# T32_ref.net
KiCad netlist of a schematic drawn in EAGLE
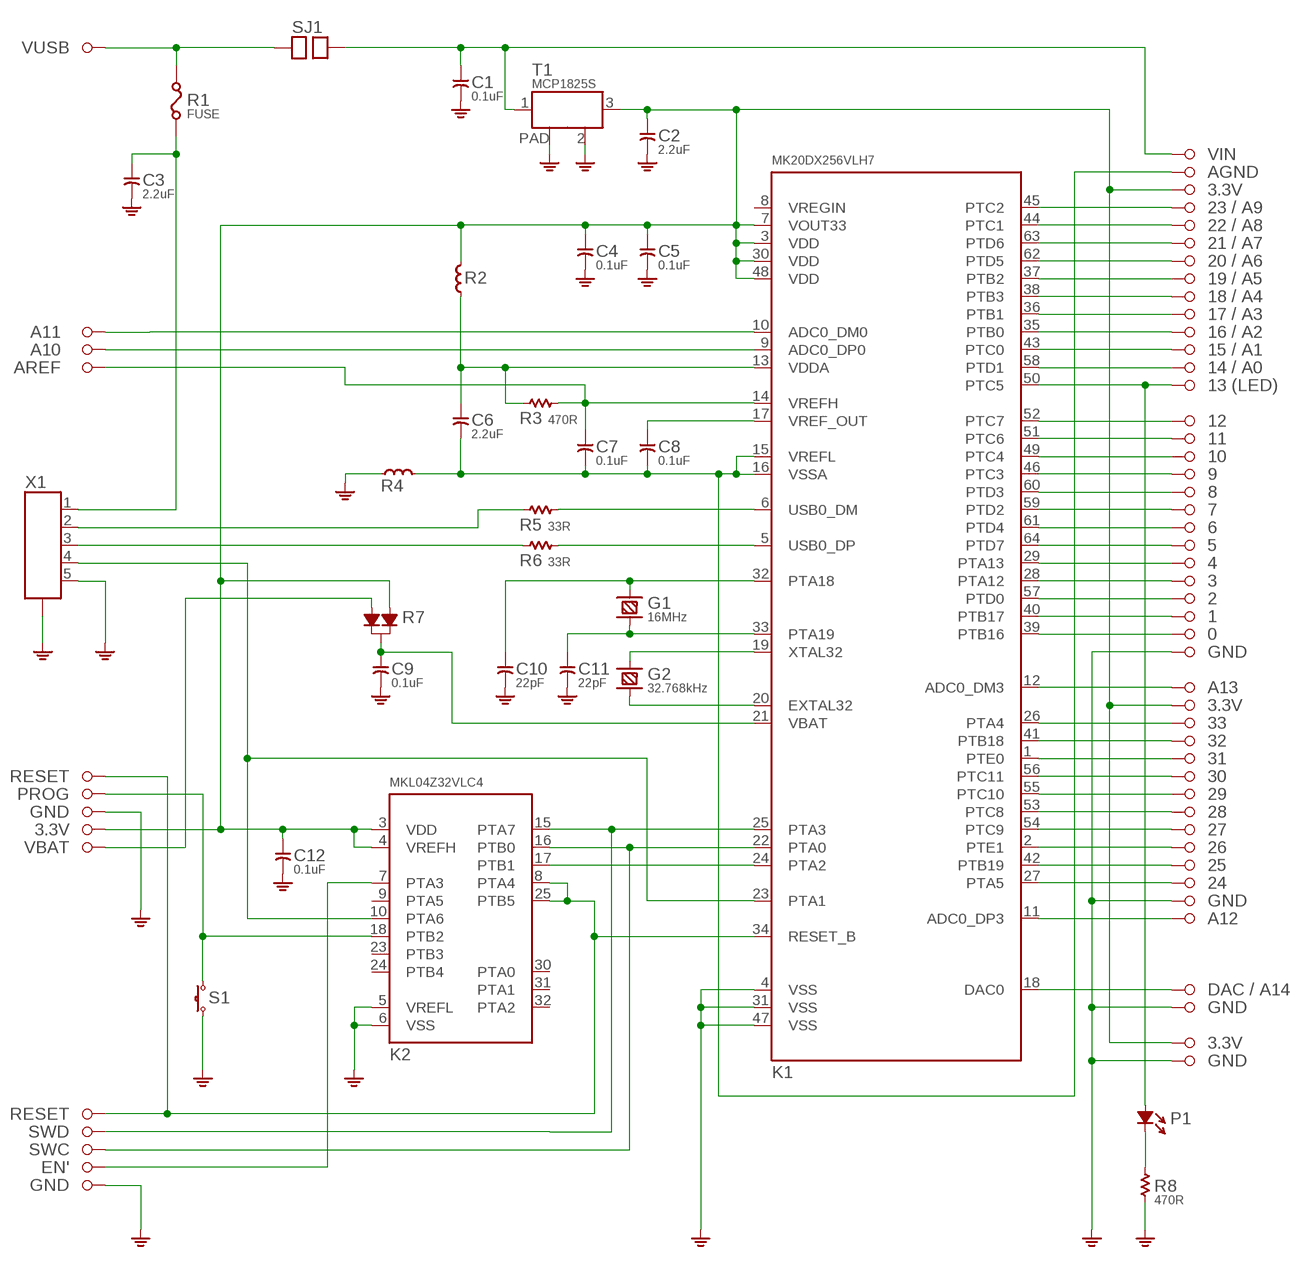
[diagram p0: schematic, sheet 1]

(export (version "E")
  (design (tool "Eeschema 10.0.6"))
  (components
    (comp (ref "C1")
      (value "0.1uF")
      (footprint "eagle-import:C0603")
      (fields (field (name "MF") "Murata Electronics") (field (name "MPN") "GRM188R71C104KA01D"))
      (libsource (lib "eagle-import") (part "CAPACITOR-0.1UF"))
    )
    (comp (ref "C2")
      (value "2.2uF")
      (footprint "eagle-import:C0805")
      (fields (field (name "MF") "Taiyo Yuden") (field (name "MPN") "TMK212B7225KG-TR"))
      (libsource (lib "eagle-import") (part "CAPACITOR-2.2UF"))
    )
    (comp (ref "C3")
      (value "2.2uF")
      (footprint "eagle-import:C0805")
      (fields (field (name "MF") "Taiyo Yuden") (field (name "MPN") "TMK212B7225KG-TR"))
      (libsource (lib "eagle-import") (part "CAPACITOR-2.2UF"))
    )
    (comp (ref "C4")
      (value "0.1uF")
      (footprint "eagle-import:C0603")
      (fields (field (name "MF") "Murata Electronics") (field (name "MPN") "GRM188R71C104KA01D"))
      (libsource (lib "eagle-import") (part "CAPACITOR-0.1UF"))
    )
    (comp (ref "C5")
      (value "0.1uF")
      (footprint "eagle-import:C0603")
      (fields (field (name "MF") "Murata Electronics") (field (name "MPN") "GRM188R71C104KA01D"))
      (libsource (lib "eagle-import") (part "CAPACITOR-0.1UF"))
    )
    (comp (ref "C6")
      (value "2.2uF")
      (footprint "eagle-import:C0805")
      (fields (field (name "MF") "Taiyo Yuden") (field (name "MPN") "TMK212B7225KG-TR"))
      (libsource (lib "eagle-import") (part "CAPACITOR-2.2UF"))
    )
    (comp (ref "C7")
      (value "0.1uF")
      (footprint "eagle-import:C0603")
      (fields (field (name "MF") "Murata Electronics") (field (name "MPN") "GRM188R71C104KA01D"))
      (libsource (lib "eagle-import") (part "CAPACITOR-0.1UF"))
    )
    (comp (ref "C8")
      (value "0.1uF")
      (footprint "eagle-import:C0603")
      (fields (field (name "MF") "Murata Electronics") (field (name "MPN") "GRM188R71C104KA01D"))
      (libsource (lib "eagle-import") (part "CAPACITOR-0.1UF"))
    )
    (comp (ref "C9")
      (value "0.1uF")
      (footprint "eagle-import:C0603")
      (fields (field (name "MF") "Murata Electronics") (field (name "MPN") "GRM188R71C104KA01D"))
      (libsource (lib "eagle-import") (part "CAPACITOR-0.1UF"))
    )
    (comp (ref "C10")
      (value "22pF")
      (footprint "eagle-import:C0603")
      (fields (field (name "MF") "Vishay / Vitramon") (field (name "MPN") "VJ0603A220JXACW1BC"))
      (libsource (lib "eagle-import") (part "CAPACITOR-22PF"))
    )
    (comp (ref "C11")
      (value "22pF")
      (footprint "eagle-import:C0603")
      (fields (field (name "MF") "Vishay / Vitramon") (field (name "MPN") "VJ0603A220JXACW1BC"))
      (libsource (lib "eagle-import") (part "CAPACITOR-22PF"))
    )
    (comp (ref "C12")
      (value "0.1uF")
      (footprint "eagle-import:C0603")
      (fields (field (name "MF") "Murata Electronics") (field (name "MPN") "GRM188R71C104KA01D"))
      (libsource (lib "eagle-import") (part "CAPACITOR-0.1UF"))
    )
    (comp (ref "G1")
      (value "16MHz")
      (footprint "eagle-import:HC49US")
      (fields (field (name "MF") "ABRACON") (field (name "MPN") "ABL-16.000MHz-B1U"))
      (libsource (lib "eagle-import") (part "CRYSTAL-HC49US"))
    )
    (comp (ref "G2")
      (value "32.768kHz")
      (footprint "eagle-import:TC26H")
      (fields (field (name "MF") "Citizen FineDevice") (field (name "MPN") " CFS206-32.768KDZF-UB"))
      (libsource (lib "eagle-import") (part "CRYSTAL-TC26H"))
    )
    (comp (ref "K1")
      (value "MK20DX256VLH7")
      (footprint "eagle-import:LQFP64-05")
      (fields (field (name "MF") "NXP"))
      (libsource (lib "eagle-import") (part "MK20DX256VLH7"))
    )
    (comp (ref "K2")
      (value "MKL04Z32VLC4")
      (footprint "eagle-import:LQFP32-08")
      (fields (field (name "MF") "PJRC") (field (name "MPN") "IC_MKL04Z32_TQFP32"))
      (libsource (lib "eagle-import") (part "MKL04Z32VLC4"))
    )
    (comp (ref "P1")
      (value "LED")
      (footprint "eagle-import:LED-0805")
      (fields (field (name "MF") "ROHM Semiconductor") (field (name "MPN") "SML-211DTT86"))
      (libsource (lib "eagle-import") (part "LED"))
    )
    (comp (ref "R1")
      (value "FUSE")
      (footprint "eagle-import:F0805")
      (fields (field (name "MF") "Bel Fuse") (field (name "MPN") "0ZCK0050FF2E"))
      (libsource (lib "eagle-import") (part "FUSE"))
    )
    (comp (ref "R2")
      (value "FERRITE")
      (footprint "eagle-import:L0603")
      (fields (field (name "MF") "Murata Electronics") (field (name "MPN") " BLM18AG601SN1D"))
      (libsource (lib "eagle-import") (part "FERRITE"))
    )
    (comp (ref "R3")
      (value "470R")
      (footprint "eagle-import:R0603")
      (fields (field (name "MF") "Vishay") (field (name "MPN") "CRCW0603470RFKEA"))
      (libsource (lib "eagle-import") (part "RESISTOR-470R"))
    )
    (comp (ref "R4")
      (value "FERRITE")
      (footprint "eagle-import:L0603")
      (fields (field (name "MF") "Murata Electronics") (field (name "MPN") " BLM18AG601SN1D"))
      (libsource (lib "eagle-import") (part "FERRITE"))
    )
    (comp (ref "R5")
      (value "33R")
      (footprint "eagle-import:R0603")
      (fields (field (name "MF") "Panasonic") (field (name "MPN") "ERJ-PA3F33R0V"))
      (libsource (lib "eagle-import") (part "RESISTOR-33R"))
    )
    (comp (ref "R6")
      (value "33R")
      (footprint "eagle-import:R0603")
      (fields (field (name "MF") "Panasonic") (field (name "MPN") "ERJ-PA3F33R0V"))
      (libsource (lib "eagle-import") (part "RESISTOR-33R"))
    )
    (comp (ref "R7")
      (value "DIODE_DUAL")
      (footprint "eagle-import:SOT-23")
      (fields (field (name "MF") "NXP Semiconductors") (field (name "MPN") "BAT54C,215"))
      (libsource (lib "eagle-import") (part "DIODE_DUAL"))
    )
    (comp (ref "R8")
      (value "470R")
      (footprint "eagle-import:R0603")
      (fields (field (name "MF") "Vishay") (field (name "MPN") "CRCW0603470RFKEA"))
      (libsource (lib "eagle-import") (part "RESISTOR-470R"))
    )
    (comp (ref "S1")
      (value "TACT_SWITCH")
      (footprint "eagle-import:ALPS_SKHH")
      (fields (field (name "MF") "ALPS") (field (name "MPN") "SKHHPKA010"))
      (libsource (lib "eagle-import") (part "TACT_SWITCH"))
    )
    (comp (ref "SJ1")
      (value "SOLDERJUMPER")
      (footprint "eagle-import:SOLDERJUMPER")
      (libsource (lib "eagle-import") (part "SOLDERJUMPER"))
    )
    (comp (ref "SX1")
      (value "PIN")
      (footprint "eagle-import:PTH_39MIL")
      (libsource (lib "eagle-import") (part "PIN"))
    )
    (comp (ref "SX2")
      (value "PIN")
      (footprint "eagle-import:PTH_39MIL")
      (libsource (lib "eagle-import") (part "PIN"))
    )
    (comp (ref "SX3")
      (value "PIN")
      (footprint "eagle-import:PTH_39MIL")
      (libsource (lib "eagle-import") (part "PIN"))
    )
    (comp (ref "SX4")
      (value "PIN")
      (footprint "eagle-import:PTH_39MIL")
      (libsource (lib "eagle-import") (part "PIN"))
    )
    (comp (ref "SX5")
      (value "PIN")
      (footprint "eagle-import:PTH_39MIL")
      (libsource (lib "eagle-import") (part "PIN"))
    )
    (comp (ref "SX6")
      (value "PIN")
      (footprint "eagle-import:PTH_39MIL")
      (libsource (lib "eagle-import") (part "PIN"))
    )
    (comp (ref "SX7")
      (value "PIN")
      (footprint "eagle-import:PTH_39MIL")
      (libsource (lib "eagle-import") (part "PIN"))
    )
    (comp (ref "SX8")
      (value "PIN")
      (footprint "eagle-import:PTH_39MIL")
      (libsource (lib "eagle-import") (part "PIN"))
    )
    (comp (ref "SX9")
      (value "PIN")
      (footprint "eagle-import:PTH_39MIL")
      (libsource (lib "eagle-import") (part "PIN"))
    )
    (comp (ref "SX10")
      (value "PIN")
      (footprint "eagle-import:PTH_39MIL")
      (libsource (lib "eagle-import") (part "PIN"))
    )
    (comp (ref "SX11")
      (value "PIN")
      (footprint "eagle-import:PTH_39MIL")
      (libsource (lib "eagle-import") (part "PIN"))
    )
    (comp (ref "SX12")
      (value "PIN")
      (footprint "eagle-import:PTH_39MIL")
      (libsource (lib "eagle-import") (part "PIN"))
    )
    (comp (ref "SX13")
      (value "PIN")
      (footprint "eagle-import:PTH_39MIL")
      (libsource (lib "eagle-import") (part "PIN"))
    )
    (comp (ref "SX14")
      (value "PIN")
      (footprint "eagle-import:PTH_39MIL")
      (libsource (lib "eagle-import") (part "PIN"))
    )
    (comp (ref "SX15")
      (value "PIN")
      (footprint "eagle-import:PTH_39MIL")
      (libsource (lib "eagle-import") (part "PIN"))
    )
    (comp (ref "SX16")
      (value "PIN")
      (footprint "eagle-import:PTH_39MIL")
      (libsource (lib "eagle-import") (part "PIN"))
    )
    (comp (ref "SX17")
      (value "PIN")
      (footprint "eagle-import:PTH_39MIL")
      (libsource (lib "eagle-import") (part "PIN"))
    )
    (comp (ref "SX18")
      (value "PIN")
      (footprint "eagle-import:PTH_39MIL")
      (libsource (lib "eagle-import") (part "PIN"))
    )
    (comp (ref "SX19")
      (value "PIN")
      (footprint "eagle-import:PTH_39MIL")
      (libsource (lib "eagle-import") (part "PIN"))
    )
    (comp (ref "SX20")
      (value "PIN")
      (footprint "eagle-import:PTH_39MIL")
      (libsource (lib "eagle-import") (part "PIN"))
    )
    (comp (ref "SX21")
      (value "PIN")
      (footprint "eagle-import:PTH_39MIL")
      (libsource (lib "eagle-import") (part "PIN"))
    )
    (comp (ref "SX22")
      (value "PIN")
      (footprint "eagle-import:PTH_39MIL")
      (libsource (lib "eagle-import") (part "PIN"))
    )
    (comp (ref "SX23")
      (value "PIN")
      (footprint "eagle-import:PTH_39MIL")
      (libsource (lib "eagle-import") (part "PIN"))
    )
    (comp (ref "SX24")
      (value "PIN")
      (footprint "eagle-import:PTH_39MIL")
      (libsource (lib "eagle-import") (part "PIN"))
    )
    (comp (ref "SX25")
      (value "PIN")
      (footprint "eagle-import:PTH_39MIL")
      (libsource (lib "eagle-import") (part "PIN"))
    )
    (comp (ref "SX26")
      (value "PIN")
      (footprint "eagle-import:PTH_39MIL")
      (libsource (lib "eagle-import") (part "PIN"))
    )
    (comp (ref "SX27")
      (value "PIN")
      (footprint "eagle-import:PTH_39MIL")
      (libsource (lib "eagle-import") (part "PIN"))
    )
    (comp (ref "SX28")
      (value "PIN")
      (footprint "eagle-import:PTH_39MIL")
      (libsource (lib "eagle-import") (part "PIN"))
    )
    (comp (ref "SX29")
      (value "PIN")
      (footprint "eagle-import:PTH_39MIL")
      (libsource (lib "eagle-import") (part "PIN"))
    )
    (comp (ref "SX30")
      (value "PIN")
      (footprint "eagle-import:PTH_39MIL")
      (libsource (lib "eagle-import") (part "PIN"))
    )
    (comp (ref "SX31")
      (value "PIN")
      (footprint "eagle-import:PTH_39MIL")
      (libsource (lib "eagle-import") (part "PIN"))
    )
    (comp (ref "SX32")
      (value "PIN")
      (footprint "eagle-import:PTH_39MIL")
      (libsource (lib "eagle-import") (part "PIN"))
    )
    (comp (ref "SX33")
      (value "PIN")
      (footprint "eagle-import:PTH_39MIL")
      (libsource (lib "eagle-import") (part "PIN"))
    )
    (comp (ref "SX34")
      (value "PIN")
      (footprint "eagle-import:PTH_39MIL")
      (libsource (lib "eagle-import") (part "PIN"))
    )
    (comp (ref "SX35")
      (value "PIN")
      (footprint "eagle-import:PTH_39MIL")
      (libsource (lib "eagle-import") (part "PIN"))
    )
    (comp (ref "SX36")
      (value "PIN")
      (footprint "eagle-import:PTH_39MIL")
      (libsource (lib "eagle-import") (part "PIN"))
    )
    (comp (ref "SX37")
      (value "PIN")
      (footprint "eagle-import:PTH_39MIL")
      (libsource (lib "eagle-import") (part "PIN"))
    )
    (comp (ref "SX38")
      (value "PIN")
      (footprint "eagle-import:PTH_39MIL")
      (libsource (lib "eagle-import") (part "PIN"))
    )
    (comp (ref "SX39")
      (value "PIN")
      (footprint "eagle-import:PTH_39MIL")
      (libsource (lib "eagle-import") (part "PIN"))
    )
    (comp (ref "SX40")
      (value "PIN")
      (footprint "eagle-import:PTH_39MIL")
      (libsource (lib "eagle-import") (part "PIN"))
    )
    (comp (ref "SX41")
      (value "PIN")
      (footprint "eagle-import:PTH_39MIL")
      (libsource (lib "eagle-import") (part "PIN"))
    )
    (comp (ref "SX42")
      (value "PIN")
      (footprint "eagle-import:PTH_39MIL")
      (libsource (lib "eagle-import") (part "PIN"))
    )
    (comp (ref "SX43")
      (value "PIN")
      (footprint "eagle-import:PTH_39MIL")
      (libsource (lib "eagle-import") (part "PIN"))
    )
    (comp (ref "SX44")
      (value "PIN")
      (footprint "eagle-import:PTH_39MIL")
      (libsource (lib "eagle-import") (part "PIN"))
    )
    (comp (ref "SX45")
      (value "PIN")
      (footprint "eagle-import:PTH_39MIL")
      (libsource (lib "eagle-import") (part "PIN"))
    )
    (comp (ref "SX46")
      (value "PIN")
      (footprint "eagle-import:PTH_39MIL")
      (libsource (lib "eagle-import") (part "PIN"))
    )
    (comp (ref "SX47")
      (value "PIN")
      (footprint "eagle-import:PTH_39MIL")
      (libsource (lib "eagle-import") (part "PIN"))
    )
    (comp (ref "SX48")
      (value "PIN")
      (footprint "eagle-import:PTH_39MIL")
      (libsource (lib "eagle-import") (part "PIN"))
    )
    (comp (ref "SX49")
      (value "PIN")
      (footprint "eagle-import:PTH_39MIL")
      (libsource (lib "eagle-import") (part "PIN"))
    )
    (comp (ref "SX50")
      (value "PIN")
      (footprint "eagle-import:PTH_39MIL")
      (libsource (lib "eagle-import") (part "PIN"))
    )
    (comp (ref "SX51")
      (value "PIN")
      (footprint "eagle-import:PTH_39MIL")
      (libsource (lib "eagle-import") (part "PIN"))
    )
    (comp (ref "SX52")
      (value "PIN")
      (footprint "eagle-import:PTH_39MIL")
      (libsource (lib "eagle-import") (part "PIN"))
    )
    (comp (ref "SX53")
      (value "PIN")
      (footprint "eagle-import:PTH_39MIL")
      (libsource (lib "eagle-import") (part "PIN"))
    )
    (comp (ref "SX54")
      (value "PIN")
      (footprint "eagle-import:PTH_39MIL")
      (libsource (lib "eagle-import") (part "PIN"))
    )
    (comp (ref "SX55")
      (value "PIN")
      (footprint "eagle-import:PTH_39MIL")
      (libsource (lib "eagle-import") (part "PIN"))
    )
    (comp (ref "SX56")
      (value "PIN")
      (footprint "eagle-import:PTH_39MIL")
      (libsource (lib "eagle-import") (part "PIN"))
    )
    (comp (ref "SX57")
      (value "PIN")
      (footprint "eagle-import:PTH_39MIL")
      (libsource (lib "eagle-import") (part "PIN"))
    )
    (comp (ref "SX58")
      (value "PIN")
      (footprint "eagle-import:PTH_39MIL")
      (libsource (lib "eagle-import") (part "PIN"))
    )
    (comp (ref "SX59")
      (value "PIN")
      (footprint "eagle-import:PTH_39MIL")
      (libsource (lib "eagle-import") (part "PIN"))
    )
    (comp (ref "SX60")
      (value "PIN")
      (footprint "eagle-import:PTH_39MIL")
      (libsource (lib "eagle-import") (part "PIN"))
    )
    (comp (ref "T1")
      (value "MCP1825S")
      (footprint "eagle-import:SOT-223")
      (fields (field (name "MF") "Microchip Technology") (field (name "MPN") "MCP1825S-3302E/DB"))
      (libsource (lib "eagle-import") (part "LDO"))
    )
    (comp (ref "X1")
      (value "MINI-USB")
      (footprint "eagle-import:MOLEX_SD-67503-010")
      (fields (field (name "MF") "MOLEX") (field (name "MPN") "0675031020"))
      (libsource (lib "eagle-import") (part "MINI-USBMOLEX_0675031230"))
    )
  )
  (nets
    (net (code "1") (name "GND") (class "Default")
      (node (ref "C1") (pin "2") (pinfunction "2_2") (pintype "passive"))
      (node (ref "C10") (pin "2") (pinfunction "2_2") (pintype "passive"))
      (node (ref "C11") (pin "2") (pinfunction "2_2") (pintype "passive"))
      (node (ref "C12") (pin "2") (pinfunction "2_2") (pintype "passive"))
      (node (ref "C2") (pin "2") (pinfunction "2_2") (pintype "passive"))
      (node (ref "C3") (pin "2") (pinfunction "2_2") (pintype "passive"))
      (node (ref "C4") (pin "2") (pinfunction "2_2") (pintype "passive"))
      (node (ref "C5") (pin "2") (pinfunction "2_2") (pintype "passive"))
      (node (ref "C9") (pin "2") (pinfunction "2_2") (pintype "passive"))
      (node (ref "K1") (pin "31") (pinfunction "VSS_31") (pintype "bidirectional"))
      (node (ref "K1") (pin "4") (pinfunction "VSS_4") (pintype "bidirectional"))
      (node (ref "K1") (pin "47") (pinfunction "VSS_47") (pintype "bidirectional"))
      (node (ref "K2") (pin "5") (pinfunction "VREFL_5") (pintype "bidirectional"))
      (node (ref "K2") (pin "6") (pinfunction "VSS_6") (pintype "bidirectional"))
      (node (ref "R4") (pin "1") (pinfunction "1_1") (pintype "passive"))
      (node (ref "R8") (pin "1") (pinfunction "1_1") (pintype "passive"))
      (node (ref "S1") (pin "3") (pinfunction "3_3") (pintype "passive"))
      (node (ref "S1") (pin "4") (pinfunction "3_4") (pintype "passive"))
      (node (ref "SX32") (pin "1") (pinfunction "P$1_1") (pintype "bidirectional"))
      (node (ref "SX42") (pin "1") (pinfunction "P$1_1") (pintype "bidirectional"))
      (node (ref "SX50") (pin "1") (pinfunction "P$1_1") (pintype "bidirectional"))
      (node (ref "SX53") (pin "1") (pinfunction "P$1_1") (pintype "bidirectional"))
      (node (ref "SX55") (pin "1") (pinfunction "P$1_1") (pintype "bidirectional"))
      (node (ref "SX60") (pin "1") (pinfunction "P$1_1") (pintype "bidirectional"))
      (node (ref "T1") (pin "2") (pinfunction "GND_2") (pintype "bidirectional"))
      (node (ref "T1") (pin "PAD") (pinfunction "PAD_PAD") (pintype "bidirectional"))
      (node (ref "X1") (pin "5") (pinfunction "5_5") (pintype "input"))
      (node (ref "X1") (pin "P$1") (pinfunction "CASE_P$1") (pintype "input"))
      (node (ref "X1") (pin "P$2") (pinfunction "CASE_P$2") (pintype "input"))
      (node (ref "X1") (pin "P$3") (pinfunction "CASE_P$3") (pintype "input"))
      (node (ref "X1") (pin "P$4") (pinfunction "CASE_P$4") (pintype "input"))
      (node (ref "X1") (pin "P$5") (pinfunction "CASE_P$5") (pintype "input"))
      (node (ref "X1") (pin "P$6") (pinfunction "CASE_P$6") (pintype "input"))
    )
    (net (code "2") (name "Net-(C3-Pad1)") (class "Default")
      (node (ref "C3") (pin "1") (pinfunction "1_1") (pintype "passive"))
      (node (ref "R1") (pin "1") (pinfunction "1_1") (pintype "bidirectional"))
      (node (ref "X1") (pin "1") (pinfunction "1_1") (pintype "input"))
    )
    (net (code "3") (name "Net-(G2-1)") (class "Default")
      (node (ref "G2") (pin "2") (pinfunction "1_2") (pintype "passive"))
      (node (ref "K1") (pin "19") (pinfunction "XTAL32_19") (pintype "bidirectional"))
    )
    (net (code "4") (name "Net-(G2-2)") (class "Default")
      (node (ref "G2") (pin "1") (pinfunction "2_1") (pintype "passive"))
      (node (ref "K1") (pin "20") (pinfunction "EXTAL32_20") (pintype "bidirectional"))
    )
    (net (code "5") (name "Net-(K1-ADC0_DM0)") (class "Default")
      (node (ref "K1") (pin "10") (pinfunction "ADC0_DM0_10") (pintype "bidirectional"))
      (node (ref "SX12") (pin "1") (pinfunction "P$1_1") (pintype "bidirectional"))
    )
    (net (code "6") (name "Net-(K1-ADC0_DM3)") (class "Default")
      (node (ref "K1") (pin "12") (pinfunction "ADC0_DM3_12") (pintype "bidirectional"))
      (node (ref "SX33") (pin "1") (pinfunction "P$1_1") (pintype "bidirectional"))
    )
    (net (code "7") (name "Net-(K1-ADC0_DP0)") (class "Default")
      (node (ref "K1") (pin "9") (pinfunction "ADC0_DP0_9") (pintype "bidirectional"))
      (node (ref "SX14") (pin "1") (pinfunction "P$1_1") (pintype "bidirectional"))
    )
    (net (code "8") (name "Net-(K1-ADC0_DP3)") (class "Default")
      (node (ref "K1") (pin "11") (pinfunction "ADC0_DP3_11") (pintype "bidirectional"))
      (node (ref "SX51") (pin "1") (pinfunction "P$1_1") (pintype "bidirectional"))
    )
    (net (code "9") (name "Net-(K1-DAC0)") (class "Default")
      (node (ref "K1") (pin "18") (pinfunction "DAC0_18") (pintype "bidirectional"))
      (node (ref "SX52") (pin "1") (pinfunction "P$1_1") (pintype "bidirectional"))
    )
    (net (code "10") (name "Net-(K1-PTA0)") (class "Default")
      (node (ref "K1") (pin "22") (pinfunction "PTA0_22") (pintype "bidirectional"))
      (node (ref "K2") (pin "16") (pinfunction "PTB0_16") (pintype "bidirectional"))
      (node (ref "SX58") (pin "1") (pinfunction "P$1_1") (pintype "bidirectional"))
    )
    (net (code "11") (name "Net-(K1-PTA1)") (class "Default")
      (node (ref "K1") (pin "23") (pinfunction "PTA1_23") (pintype "bidirectional"))
      (node (ref "K2") (pin "10") (pinfunction "PTA6_10") (pintype "bidirectional"))
      (node (ref "X1") (pin "4") (pinfunction "4_4") (pintype "input"))
    )
    (net (code "12") (name "Net-(K1-PTA2)") (class "Default")
      (node (ref "K1") (pin "24") (pinfunction "PTA2_24") (pintype "bidirectional"))
      (node (ref "K2") (pin "17") (pinfunction "PTB1_17") (pintype "bidirectional"))
    )
    (net (code "13") (name "Net-(K1-PTA3)") (class "Default")
      (node (ref "K1") (pin "25") (pinfunction "PTA3_25") (pintype "bidirectional"))
      (node (ref "K2") (pin "15") (pinfunction "PTA7_15") (pintype "bidirectional"))
      (node (ref "SX57") (pin "1") (pinfunction "P$1_1") (pintype "bidirectional"))
    )
    (net (code "14") (name "Net-(K1-PTA4)") (class "Default")
      (node (ref "K1") (pin "26") (pinfunction "PTA4_26") (pintype "bidirectional"))
      (node (ref "SX35") (pin "1") (pinfunction "P$1_1") (pintype "bidirectional"))
    )
    (net (code "15") (name "Net-(K1-PTA5)") (class "Default")
      (node (ref "K1") (pin "27") (pinfunction "PTA5_27") (pintype "bidirectional"))
      (node (ref "SX49") (pin "1") (pinfunction "P$1_1") (pintype "bidirectional"))
    )
    (net (code "16") (name "Net-(K1-PTA12)") (class "Default")
      (node (ref "K1") (pin "28") (pinfunction "PTA12_28") (pintype "bidirectional"))
      (node (ref "SX28") (pin "1") (pinfunction "P$1_1") (pintype "bidirectional"))
    )
    (net (code "17") (name "Net-(K1-PTA13)") (class "Default")
      (node (ref "K1") (pin "29") (pinfunction "PTA13_29") (pintype "bidirectional"))
      (node (ref "SX27") (pin "1") (pinfunction "P$1_1") (pintype "bidirectional"))
    )
    (net (code "18") (name "Net-(K1-PTA18)") (class "Default")
      (node (ref "C10") (pin "1") (pinfunction "1_1") (pintype "passive"))
      (node (ref "G1") (pin "1") (pinfunction "1_1") (pintype "passive"))
      (node (ref "K1") (pin "32") (pinfunction "PTA18_32") (pintype "bidirectional"))
    )
    (net (code "19") (name "Net-(K1-PTA19)") (class "Default")
      (node (ref "C11") (pin "1") (pinfunction "1_1") (pintype "passive"))
      (node (ref "G1") (pin "2") (pinfunction "2_2") (pintype "passive"))
      (node (ref "K1") (pin "33") (pinfunction "PTA19_33") (pintype "bidirectional"))
    )
    (net (code "20") (name "Net-(K1-PTB0)") (class "Default")
      (node (ref "K1") (pin "35") (pinfunction "PTB0_35") (pintype "bidirectional"))
      (node (ref "SX13") (pin "1") (pinfunction "P$1_1") (pintype "bidirectional"))
    )
    (net (code "21") (name "Net-(K1-PTB1)") (class "Default")
      (node (ref "K1") (pin "36") (pinfunction "PTB1_36") (pintype "bidirectional"))
      (node (ref "SX11") (pin "1") (pinfunction "P$1_1") (pintype "bidirectional"))
    )
    (net (code "22") (name "Net-(K1-PTB2)") (class "Default")
      (node (ref "K1") (pin "37") (pinfunction "PTB2_37") (pintype "bidirectional"))
      (node (ref "SX9") (pin "1") (pinfunction "P$1_1") (pintype "bidirectional"))
    )
    (net (code "23") (name "Net-(K1-PTB3)") (class "Default")
      (node (ref "K1") (pin "38") (pinfunction "PTB3_38") (pintype "bidirectional"))
      (node (ref "SX10") (pin "1") (pinfunction "P$1_1") (pintype "bidirectional"))
    )
    (net (code "24") (name "Net-(K1-PTB16)") (class "Default")
      (node (ref "K1") (pin "39") (pinfunction "PTB16_39") (pintype "bidirectional"))
      (node (ref "SX31") (pin "1") (pinfunction "P$1_1") (pintype "bidirectional"))
    )
    (net (code "25") (name "Net-(K1-PTB17)") (class "Default")
      (node (ref "K1") (pin "40") (pinfunction "PTB17_40") (pintype "bidirectional"))
      (node (ref "SX30") (pin "1") (pinfunction "P$1_1") (pintype "bidirectional"))
    )
    (net (code "26") (name "Net-(K1-PTB18)") (class "Default")
      (node (ref "K1") (pin "41") (pinfunction "PTB18_41") (pintype "bidirectional"))
      (node (ref "SX36") (pin "1") (pinfunction "P$1_1") (pintype "bidirectional"))
    )
    (net (code "27") (name "Net-(K1-PTB19)") (class "Default")
      (node (ref "K1") (pin "42") (pinfunction "PTB19_42") (pintype "bidirectional"))
      (node (ref "SX48") (pin "1") (pinfunction "P$1_1") (pintype "bidirectional"))
    )
    (net (code "28") (name "Net-(K1-PTC0)") (class "Default")
      (node (ref "K1") (pin "43") (pinfunction "PTC0_43") (pintype "bidirectional"))
      (node (ref "SX15") (pin "1") (pinfunction "P$1_1") (pintype "bidirectional"))
    )
    (net (code "29") (name "Net-(K1-PTC1)") (class "Default")
      (node (ref "K1") (pin "44") (pinfunction "PTC1_44") (pintype "bidirectional"))
      (node (ref "SX6") (pin "1") (pinfunction "P$1_1") (pintype "bidirectional"))
    )
    (net (code "30") (name "Net-(K1-PTC2)") (class "Default")
      (node (ref "K1") (pin "45") (pinfunction "PTC2_45") (pintype "bidirectional"))
      (node (ref "SX5") (pin "1") (pinfunction "P$1_1") (pintype "bidirectional"))
    )
    (net (code "31") (name "Net-(K1-PTC3)") (class "Default")
      (node (ref "K1") (pin "46") (pinfunction "PTC3_46") (pintype "bidirectional"))
      (node (ref "SX22") (pin "1") (pinfunction "P$1_1") (pintype "bidirectional"))
    )
    (net (code "32") (name "Net-(K1-PTC4)") (class "Default")
      (node (ref "K1") (pin "49") (pinfunction "PTC4_49") (pintype "bidirectional"))
      (node (ref "SX21") (pin "1") (pinfunction "P$1_1") (pintype "bidirectional"))
    )
    (net (code "33") (name "Net-(K1-PTC5)") (class "Default")
      (node (ref "K1") (pin "50") (pinfunction "PTC5_50") (pintype "bidirectional"))
      (node (ref "P1") (pin "+") (pinfunction "+_+") (pintype "passive"))
      (node (ref "SX18") (pin "1") (pinfunction "P$1_1") (pintype "bidirectional"))
    )
    (net (code "34") (name "Net-(K1-PTC6)") (class "Default")
      (node (ref "K1") (pin "51") (pinfunction "PTC6_51") (pintype "bidirectional"))
      (node (ref "SX20") (pin "1") (pinfunction "P$1_1") (pintype "bidirectional"))
    )
    (net (code "35") (name "Net-(K1-PTC7)") (class "Default")
      (node (ref "K1") (pin "52") (pinfunction "PTC7_52") (pintype "bidirectional"))
      (node (ref "SX19") (pin "1") (pinfunction "P$1_1") (pintype "bidirectional"))
    )
    (net (code "36") (name "Net-(K1-PTC8)") (class "Default")
      (node (ref "K1") (pin "53") (pinfunction "PTC8_53") (pintype "bidirectional"))
      (node (ref "SX43") (pin "1") (pinfunction "P$1_1") (pintype "bidirectional"))
    )
    (net (code "37") (name "Net-(K1-PTC9)") (class "Default")
      (node (ref "K1") (pin "54") (pinfunction "PTC9_54") (pintype "bidirectional"))
      (node (ref "SX45") (pin "1") (pinfunction "P$1_1") (pintype "bidirectional"))
    )
    (net (code "38") (name "Net-(K1-PTC10)") (class "Default")
      (node (ref "K1") (pin "55") (pinfunction "PTC10_55") (pintype "bidirectional"))
      (node (ref "SX41") (pin "1") (pinfunction "P$1_1") (pintype "bidirectional"))
    )
    (net (code "39") (name "Net-(K1-PTC11)") (class "Default")
      (node (ref "K1") (pin "56") (pinfunction "PTC11_56") (pintype "bidirectional"))
      (node (ref "SX39") (pin "1") (pinfunction "P$1_1") (pintype "bidirectional"))
    )
    (net (code "40") (name "Net-(K1-PTD0)") (class "Default")
      (node (ref "K1") (pin "57") (pinfunction "PTD0_57") (pintype "bidirectional"))
      (node (ref "SX29") (pin "1") (pinfunction "P$1_1") (pintype "bidirectional"))
    )
    (net (code "41") (name "Net-(K1-PTD1)") (class "Default")
      (node (ref "K1") (pin "58") (pinfunction "PTD1_58") (pintype "bidirectional"))
      (node (ref "SX17") (pin "1") (pinfunction "P$1_1") (pintype "bidirectional"))
    )
    (net (code "42") (name "Net-(K1-PTD2)") (class "Default")
      (node (ref "K1") (pin "59") (pinfunction "PTD2_59") (pintype "bidirectional"))
      (node (ref "SX24") (pin "1") (pinfunction "P$1_1") (pintype "bidirectional"))
    )
    (net (code "43") (name "Net-(K1-PTD3)") (class "Default")
      (node (ref "K1") (pin "60") (pinfunction "PTD3_60") (pintype "bidirectional"))
      (node (ref "SX23") (pin "1") (pinfunction "P$1_1") (pintype "bidirectional"))
    )
    (net (code "44") (name "Net-(K1-PTD4)") (class "Default")
      (node (ref "K1") (pin "61") (pinfunction "PTD4_61") (pintype "bidirectional"))
      (node (ref "SX25") (pin "1") (pinfunction "P$1_1") (pintype "bidirectional"))
    )
    (net (code "45") (name "Net-(K1-PTD5)") (class "Default")
      (node (ref "K1") (pin "62") (pinfunction "PTD5_62") (pintype "bidirectional"))
      (node (ref "SX8") (pin "1") (pinfunction "P$1_1") (pintype "bidirectional"))
    )
    (net (code "46") (name "Net-(K1-PTD6)") (class "Default")
      (node (ref "K1") (pin "63") (pinfunction "PTD6_63") (pintype "bidirectional"))
      (node (ref "SX7") (pin "1") (pinfunction "P$1_1") (pintype "bidirectional"))
    )
    (net (code "47") (name "Net-(K1-PTD7)") (class "Default")
      (node (ref "K1") (pin "64") (pinfunction "PTD7_64") (pintype "bidirectional"))
      (node (ref "SX26") (pin "1") (pinfunction "P$1_1") (pintype "bidirectional"))
    )
    (net (code "48") (name "Net-(K1-PTE0)") (class "Default")
      (node (ref "K1") (pin "1") (pinfunction "PTE0_1") (pintype "bidirectional"))
      (node (ref "SX37") (pin "1") (pinfunction "P$1_1") (pintype "bidirectional"))
    )
    (net (code "49") (name "Net-(K1-PTE1)") (class "Default")
      (node (ref "K1") (pin "2") (pinfunction "PTE1_2") (pintype "bidirectional"))
      (node (ref "SX47") (pin "1") (pinfunction "P$1_1") (pintype "bidirectional"))
    )
    (net (code "50") (name "Net-(K1-RESET_B)") (class "Default")
      (node (ref "K1") (pin "34") (pinfunction "RESET_B_34") (pintype "bidirectional"))
      (node (ref "K2") (pin "25") (pinfunction "PTB5_25") (pintype "bidirectional"))
      (node (ref "K2") (pin "8") (pinfunction "PTA4_8") (pintype "bidirectional"))
      (node (ref "SX38") (pin "1") (pinfunction "P$1_1") (pintype "bidirectional"))
      (node (ref "SX56") (pin "1") (pinfunction "P$1_1") (pintype "bidirectional"))
    )
    (net (code "51") (name "Net-(K1-USB0_DM)") (class "Default")
      (node (ref "K1") (pin "6") (pinfunction "USB0_DM_6") (pintype "bidirectional"))
      (node (ref "R5") (pin "2") (pinfunction "2_2") (pintype "passive"))
    )
    (net (code "52") (name "Net-(K1-USB0_DP)") (class "Default")
      (node (ref "K1") (pin "5") (pinfunction "USB0_DP_5") (pintype "bidirectional"))
      (node (ref "R6") (pin "2") (pinfunction "2_2") (pintype "passive"))
    )
    (net (code "53") (name "Net-(K1-VBAT)") (class "Default")
      (node (ref "C9") (pin "1") (pinfunction "1_1") (pintype "passive"))
      (node (ref "K1") (pin "21") (pinfunction "VBAT_21") (pintype "bidirectional"))
      (node (ref "R7") (pin "3") (pinfunction "3_3") (pintype "bidirectional"))
    )
    (net (code "54") (name "Net-(K1-VDDA)") (class "Default")
      (node (ref "C6") (pin "1") (pinfunction "1_1") (pintype "passive"))
      (node (ref "K1") (pin "13") (pinfunction "VDDA_13") (pintype "bidirectional"))
      (node (ref "R2") (pin "1") (pinfunction "1_1") (pintype "passive"))
      (node (ref "R3") (pin "1") (pinfunction "1_1") (pintype "passive"))
    )
    (net (code "55") (name "Net-(K1-VOUT33)") (class "Default")
      (node (ref "C12") (pin "1") (pinfunction "1_1") (pintype "passive"))
      (node (ref "C2") (pin "1") (pinfunction "1_1") (pintype "passive"))
      (node (ref "C4") (pin "1") (pinfunction "1_1") (pintype "passive"))
      (node (ref "C5") (pin "1") (pinfunction "1_1") (pintype "passive"))
      (node (ref "K1") (pin "3") (pinfunction "VDD_3") (pintype "bidirectional"))
      (node (ref "K1") (pin "30") (pinfunction "VDD_30") (pintype "bidirectional"))
      (node (ref "K1") (pin "48") (pinfunction "VDD_48") (pintype "bidirectional"))
      (node (ref "K1") (pin "7") (pinfunction "VOUT33_7") (pintype "bidirectional"))
      (node (ref "K2") (pin "3") (pinfunction "VDD_3") (pintype "bidirectional"))
      (node (ref "K2") (pin "4") (pinfunction "VREFH_4") (pintype "bidirectional"))
      (node (ref "R2") (pin "2") (pinfunction "2_2") (pintype "passive"))
      (node (ref "R7") (pin "1") (pinfunction "1_1") (pintype "bidirectional"))
      (node (ref "SX34") (pin "1") (pinfunction "P$1_1") (pintype "bidirectional"))
      (node (ref "SX4") (pin "1") (pinfunction "P$1_1") (pintype "bidirectional"))
      (node (ref "SX44") (pin "1") (pinfunction "P$1_1") (pintype "bidirectional"))
      (node (ref "SX54") (pin "1") (pinfunction "P$1_1") (pintype "bidirectional"))
      (node (ref "T1") (pin "3") (pinfunction "OUT_3") (pintype "bidirectional"))
    )
    (net (code "56") (name "Net-(K1-VREFH)") (class "Default")
      (node (ref "C7") (pin "1") (pinfunction "1_1") (pintype "passive"))
      (node (ref "K1") (pin "14") (pinfunction "VREFH_14") (pintype "bidirectional"))
      (node (ref "R3") (pin "2") (pinfunction "2_2") (pintype "passive"))
      (node (ref "SX16") (pin "1") (pinfunction "P$1_1") (pintype "bidirectional"))
    )
    (net (code "57") (name "Net-(K1-VREFL)") (class "Default")
      (node (ref "C6") (pin "2") (pinfunction "2_2") (pintype "passive"))
      (node (ref "C7") (pin "2") (pinfunction "2_2") (pintype "passive"))
      (node (ref "C8") (pin "2") (pinfunction "2_2") (pintype "passive"))
      (node (ref "K1") (pin "15") (pinfunction "VREFL_15") (pintype "bidirectional"))
      (node (ref "K1") (pin "16") (pinfunction "VSSA_16") (pintype "bidirectional"))
      (node (ref "R4") (pin "2") (pinfunction "2_2") (pintype "passive"))
      (node (ref "SX3") (pin "1") (pinfunction "P$1_1") (pintype "bidirectional"))
    )
    (net (code "58") (name "Net-(K1-VREF_OUT)") (class "Default")
      (node (ref "C8") (pin "1") (pinfunction "1_1") (pintype "passive"))
      (node (ref "K1") (pin "17") (pinfunction "VREF_OUT_17") (pintype "bidirectional"))
    )
    (net (code "59") (name "Net-(K2-PTA3)") (class "Default")
      (node (ref "K2") (pin "7") (pinfunction "PTA3_7") (pintype "bidirectional"))
      (node (ref "SX59") (pin "1") (pinfunction "P$1_1") (pintype "bidirectional"))
    )
    (net (code "60") (name "Net-(K2-PTB2)") (class "Default")
      (node (ref "K2") (pin "18") (pinfunction "PTB2_18") (pintype "bidirectional"))
      (node (ref "S1") (pin "1") (pinfunction "1_1") (pintype "passive"))
      (node (ref "S1") (pin "2") (pinfunction "1_2") (pintype "passive"))
      (node (ref "SX40") (pin "1") (pinfunction "P$1_1") (pintype "bidirectional"))
    )
    (net (code "61") (name "Net-(P1-Pad-)") (class "Default")
      (node (ref "P1") (pin "-") (pinfunction "-_-") (pintype "passive"))
      (node (ref "R8") (pin "2") (pinfunction "2_2") (pintype "passive"))
    )
    (net (code "62") (name "Net-(R5-Pad1)") (class "Default")
      (node (ref "R5") (pin "1") (pinfunction "1_1") (pintype "passive"))
      (node (ref "X1") (pin "2") (pinfunction "2_2") (pintype "input"))
    )
    (net (code "63") (name "Net-(R6-Pad1)") (class "Default")
      (node (ref "R6") (pin "1") (pinfunction "1_1") (pintype "passive"))
      (node (ref "X1") (pin "3") (pinfunction "3_3") (pintype "input"))
    )
    (net (code "64") (name "Net-(SX1-P$1)") (class "Default")
      (node (ref "R1") (pin "2") (pinfunction "2_2") (pintype "bidirectional"))
      (node (ref "SJ1") (pin "1") (pinfunction "1_1") (pintype "passive"))
      (node (ref "SX1") (pin "1") (pinfunction "P$1_1") (pintype "bidirectional"))
    )
    (net (code "65") (name "Net-(SX2-P$1)") (class "Default")
      (node (ref "C1") (pin "1") (pinfunction "1_1") (pintype "passive"))
      (node (ref "SJ1") (pin "2") (pinfunction "2_2") (pintype "passive"))
      (node (ref "SX2") (pin "1") (pinfunction "P$1_1") (pintype "bidirectional"))
      (node (ref "T1") (pin "1") (pinfunction "IN_1") (pintype "bidirectional"))
    )
    (net (code "66") (name "Net-(SX46-P$1)") (class "Default")
      (node (ref "R7") (pin "2") (pinfunction "2_2") (pintype "bidirectional"))
      (node (ref "SX46") (pin "1") (pinfunction "P$1_1") (pintype "bidirectional"))
    )
    (net (code "67") (name "unconnected-(K1-VREGIN-Pad8)") (class "Default")
      (node (ref "K1") (pin "8") (pinfunction "VREGIN_8") (pintype "bidirectional"))
    )
    (net (code "68") (name "unconnected-(K2-PTA0-Pad30)") (class "Default")
      (node (ref "K2") (pin "30") (pinfunction "PTA0_30") (pintype "bidirectional"))
    )
    (net (code "69") (name "unconnected-(K2-PTA1-Pad31)") (class "Default")
      (node (ref "K2") (pin "31") (pinfunction "PTA1_31") (pintype "bidirectional"))
    )
    (net (code "70") (name "unconnected-(K2-PTA2-Pad32)") (class "Default")
      (node (ref "K2") (pin "32") (pinfunction "PTA2_32") (pintype "bidirectional"))
    )
    (net (code "71") (name "unconnected-(K2-PTA5-Pad9)") (class "Default")
      (node (ref "K2") (pin "9") (pinfunction "PTA5_9") (pintype "bidirectional"))
    )
    (net (code "72") (name "unconnected-(K2-PTB3-Pad23)") (class "Default")
      (node (ref "K2") (pin "23") (pinfunction "PTB3_23") (pintype "bidirectional"))
    )
    (net (code "73") (name "unconnected-(K2-PTB4-Pad24)") (class "Default")
      (node (ref "K2") (pin "24") (pinfunction "PTB4_24") (pintype "bidirectional"))
    )
  )
)
